# design.net
KiCad netlist of a schematic drawn in Altium Designer
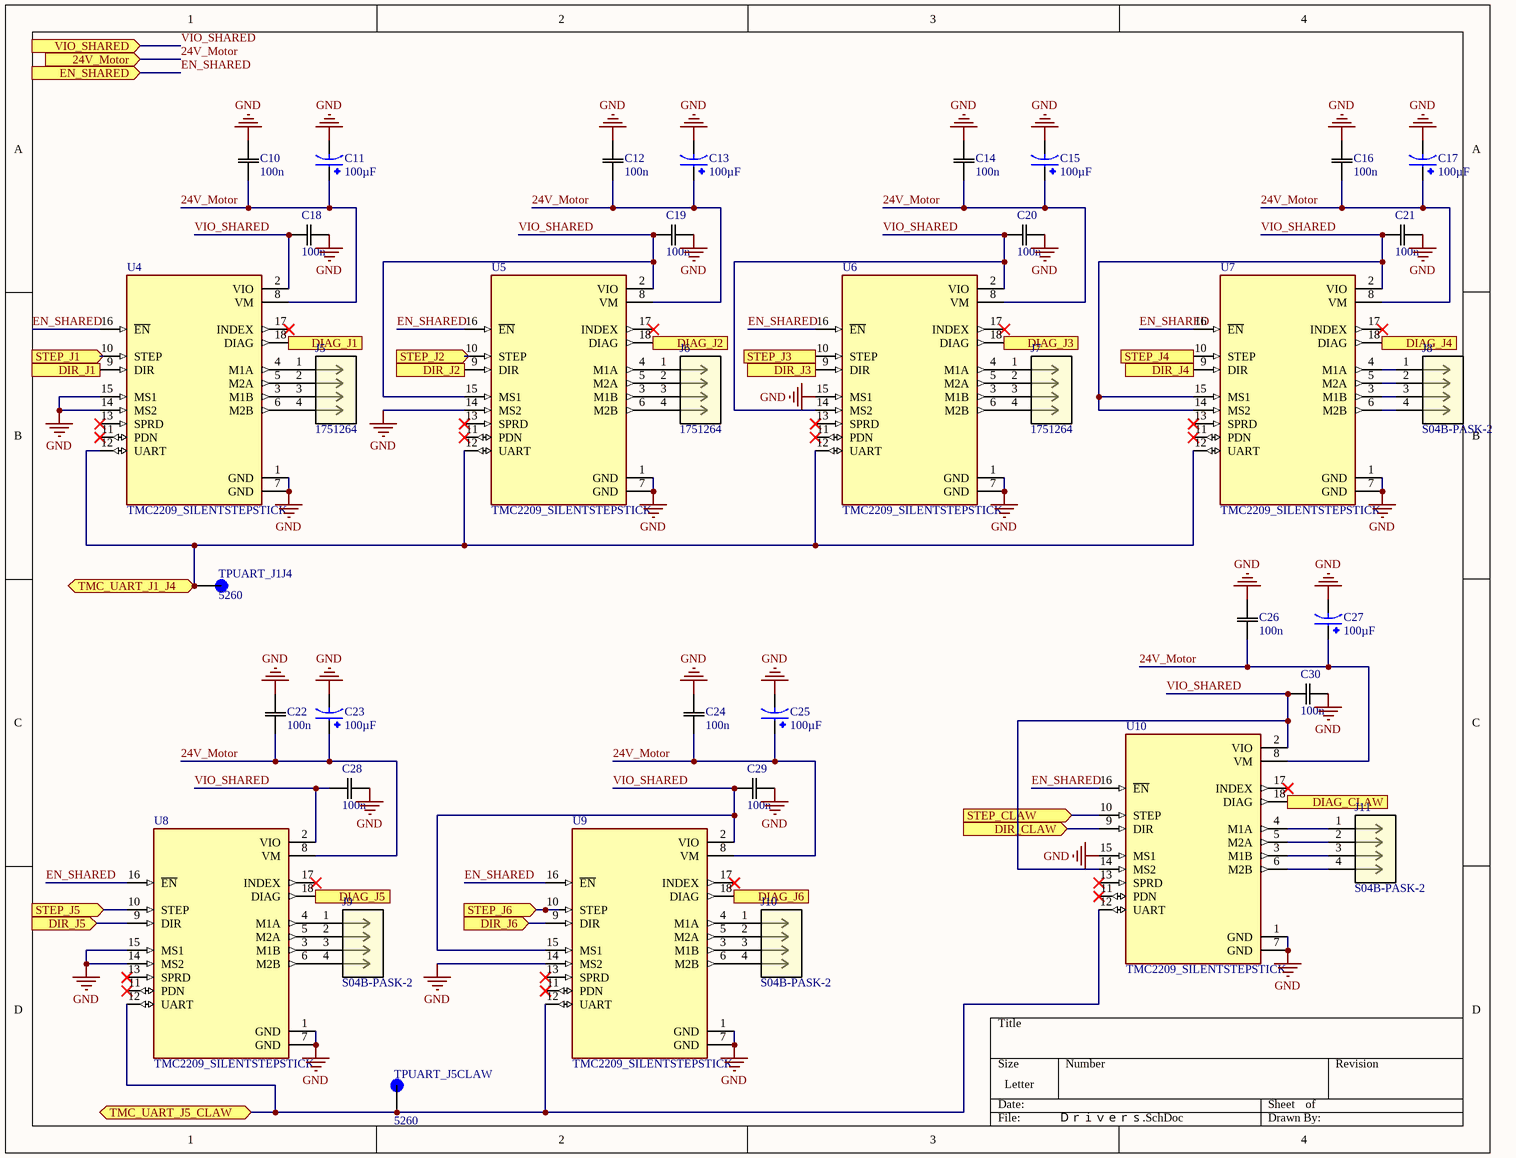
[diagram p0: Ｄｒｉｖｅｒｓ.SchDoc]

(export (version "E")
  (design (tool "Eeschema 10.0.6"))
  (components
    (comp (ref "C10")
      (value "CL21B104KCCWPNC")
      (footprint "CAP_CL_21_SAM")
      (description "No Description Available")
      (fields
        (field (name "CAPACITANCE") "100n")
        (field (name "COPYRIGHT") "Copyright (C) 2026 Ultra Librarian. All rights reserved.")
      )
      (libsource (lib "CL21B104KCCWPNC") (part "CL21B104KCCWPNC"))
    )
    (comp (ref "C11")
      (value "100µF")
      (footprint "CAPPRD500W60D800H1150")
      (description "Cap Aluminum 100uF 50V 20% (8 X 11.5mm) Radial 5mm 870mA 6000 hr 105C Ammo Pack")
      (fields (field (name "MP") "EEU-FR1H101B") (field (name "MF") "Panasonic Electronic"))
      (libsource (lib "Chen-Shi Liou") (part "EEUFR1H101B"))
    )
    (comp (ref "C12")
      (value "CL21B104KCCWPNC")
      (footprint "CAP_CL_21_SAM")
      (description "No Description Available")
      (fields
        (field (name "CAPACITANCE") "100n")
        (field (name "COPYRIGHT") "Copyright (C) 2026 Ultra Librarian. All rights reserved.")
      )
      (libsource (lib "CL21B104KCCWPNC") (part "CL21B104KCCWPNC"))
    )
    (comp (ref "C13")
      (value "100µF")
      (footprint "CAPPRD500W60D800H1150")
      (description "Cap Aluminum 100uF 50V 20% (8 X 11.5mm) Radial 5mm 870mA 6000 hr 105C Ammo Pack")
      (fields (field (name "MP") "EEU-FR1H101B") (field (name "MF") "Panasonic Electronic"))
      (libsource (lib "Chen-Shi Liou") (part "EEUFR1H101B"))
    )
    (comp (ref "C14")
      (value "CL21B104KCCWPNC")
      (footprint "CAP_CL_21_SAM")
      (description "No Description Available")
      (fields
        (field (name "CAPACITANCE") "100n")
        (field (name "COPYRIGHT") "Copyright (C) 2026 Ultra Librarian. All rights reserved.")
      )
      (libsource (lib "CL21B104KCCWPNC") (part "CL21B104KCCWPNC"))
    )
    (comp (ref "C15")
      (value "100µF")
      (footprint "CAPPRD500W60D800H1150")
      (description "Cap Aluminum 100uF 50V 20% (8 X 11.5mm) Radial 5mm 870mA 6000 hr 105C Ammo Pack")
      (fields (field (name "MP") "EEU-FR1H101B") (field (name "MF") "Panasonic Electronic"))
      (libsource (lib "Chen-Shi Liou") (part "EEUFR1H101B"))
    )
    (comp (ref "C16")
      (value "CL21B104KCCWPNC")
      (footprint "CAP_CL_21_SAM")
      (description "No Description Available")
      (fields
        (field (name "CAPACITANCE") "100n")
        (field (name "COPYRIGHT") "Copyright (C) 2026 Ultra Librarian. All rights reserved.")
      )
      (libsource (lib "CL21B104KCCWPNC") (part "CL21B104KCCWPNC"))
    )
    (comp (ref "C17")
      (value "100µF")
      (footprint "CAPPRD500W60D800H1150")
      (description "Cap Aluminum 100uF 50V 20% (8 X 11.5mm) Radial 5mm 870mA 6000 hr 105C Ammo Pack")
      (fields (field (name "MP") "EEU-FR1H101B") (field (name "MF") "Panasonic Electronic"))
      (libsource (lib "Chen-Shi Liou") (part "EEUFR1H101B"))
    )
    (comp (ref "C18")
      (value "CL21B104KCCWPNC")
      (footprint "CAP_CL_21_SAM")
      (description "No Description Available")
      (fields
        (field (name "CAPACITANCE") "100n")
        (field (name "COPYRIGHT") "Copyright (C) 2026 Ultra Librarian. All rights reserved.")
      )
      (libsource (lib "CL21B104KCCWPNC") (part "CL21B104KCCWPNC"))
    )
    (comp (ref "C19")
      (value "CL21B104KCCWPNC")
      (footprint "CAP_CL_21_SAM")
      (description "No Description Available")
      (fields
        (field (name "CAPACITANCE") "100n")
        (field (name "COPYRIGHT") "Copyright (C) 2026 Ultra Librarian. All rights reserved.")
      )
      (libsource (lib "CL21B104KCCWPNC") (part "CL21B104KCCWPNC"))
    )
    (comp (ref "C20")
      (value "CL21B104KCCWPNC")
      (footprint "CAP_CL_21_SAM")
      (description "No Description Available")
      (fields
        (field (name "CAPACITANCE") "100n")
        (field (name "COPYRIGHT") "Copyright (C) 2026 Ultra Librarian. All rights reserved.")
      )
      (libsource (lib "CL21B104KCCWPNC") (part "CL21B104KCCWPNC"))
    )
    (comp (ref "C21")
      (value "CL21B104KCCWPNC")
      (footprint "CAP_CL_21_SAM")
      (description "No Description Available")
      (fields
        (field (name "CAPACITANCE") "100n")
        (field (name "COPYRIGHT") "Copyright (C) 2026 Ultra Librarian. All rights reserved.")
      )
      (libsource (lib "CL21B104KCCWPNC") (part "CL21B104KCCWPNC"))
    )
    (comp (ref "C22")
      (value "CL21B104KCCWPNC")
      (footprint "CAP_CL_21_SAM")
      (description "No Description Available")
      (fields
        (field (name "CAPACITANCE") "100n")
        (field (name "COPYRIGHT") "Copyright (C) 2026 Ultra Librarian. All rights reserved.")
      )
      (libsource (lib "CL21B104KCCWPNC") (part "CL21B104KCCWPNC"))
    )
    (comp (ref "C23")
      (value "100µF")
      (footprint "CAPPRD500W60D800H1150")
      (description "Cap Aluminum 100uF 50V 20% (8 X 11.5mm) Radial 5mm 870mA 6000 hr 105C Ammo Pack")
      (fields (field (name "MP") "EEU-FR1H101B") (field (name "MF") "Panasonic Electronic"))
      (libsource (lib "Chen-Shi Liou") (part "EEUFR1H101B"))
    )
    (comp (ref "C24")
      (value "CL21B104KCCWPNC")
      (footprint "CAP_CL_21_SAM")
      (description "No Description Available")
      (fields
        (field (name "CAPACITANCE") "100n")
        (field (name "COPYRIGHT") "Copyright (C) 2026 Ultra Librarian. All rights reserved.")
      )
      (libsource (lib "CL21B104KCCWPNC") (part "CL21B104KCCWPNC"))
    )
    (comp (ref "C25")
      (value "100µF")
      (footprint "CAPPRD500W60D800H1150")
      (description "Cap Aluminum 100uF 50V 20% (8 X 11.5mm) Radial 5mm 870mA 6000 hr 105C Ammo Pack")
      (fields (field (name "MP") "EEU-FR1H101B") (field (name "MF") "Panasonic Electronic"))
      (libsource (lib "Chen-Shi Liou") (part "EEUFR1H101B"))
    )
    (comp (ref "C26")
      (value "CL21B104KCCWPNC")
      (footprint "CAP_CL_21_SAM")
      (description "No Description Available")
      (fields
        (field (name "CAPACITANCE") "100n")
        (field (name "COPYRIGHT") "Copyright (C) 2026 Ultra Librarian. All rights reserved.")
      )
      (libsource (lib "CL21B104KCCWPNC") (part "CL21B104KCCWPNC"))
    )
    (comp (ref "C27")
      (value "100µF")
      (footprint "CAPPRD500W60D800H1150")
      (description "Cap Aluminum 100uF 50V 20% (8 X 11.5mm) Radial 5mm 870mA 6000 hr 105C Ammo Pack")
      (fields (field (name "MP") "EEU-FR1H101B") (field (name "MF") "Panasonic Electronic"))
      (libsource (lib "Chen-Shi Liou") (part "EEUFR1H101B"))
    )
    (comp (ref "C28")
      (value "CL21B104KCCWPNC")
      (footprint "CAP_CL_21_SAM")
      (description "No Description Available")
      (fields
        (field (name "CAPACITANCE") "100n")
        (field (name "COPYRIGHT") "Copyright (C) 2026 Ultra Librarian. All rights reserved.")
      )
      (libsource (lib "CL21B104KCCWPNC") (part "CL21B104KCCWPNC"))
    )
    (comp (ref "C29")
      (value "CL21B104KCCWPNC")
      (footprint "CAP_CL_21_SAM")
      (description "No Description Available")
      (fields
        (field (name "CAPACITANCE") "100n")
        (field (name "COPYRIGHT") "Copyright (C) 2026 Ultra Librarian. All rights reserved.")
      )
      (libsource (lib "CL21B104KCCWPNC") (part "CL21B104KCCWPNC"))
    )
    (comp (ref "C30")
      (value "CL21B104KCCWPNC")
      (footprint "CAP_CL_21_SAM")
      (description "No Description Available")
      (fields
        (field (name "CAPACITANCE") "100n")
        (field (name "COPYRIGHT") "Copyright (C) 2026 Ultra Librarian. All rights reserved.")
      )
      (libsource (lib "CL21B104KCCWPNC") (part "CL21B104KCCWPNC"))
    )
    (comp (ref "J5")
      (value "1751264")
      (footprint "CONN_1751264_PXC")
      (fields (field (name "COPYRIGHT") "Copyright (C) 2025 Ultra Librarian. All rights reserved."))
      (libsource (lib "1751264") (part "1751264"))
    )
    (comp (ref "J6")
      (value "1751264")
      (footprint "CONN_1751264_PXC")
      (fields (field (name "COPYRIGHT") "Copyright (C) 2025 Ultra Librarian. All rights reserved."))
      (libsource (lib "1751264") (part "1751264"))
    )
    (comp (ref "J7")
      (value "1751264")
      (footprint "CONN_1751264_PXC")
      (fields (field (name "COPYRIGHT") "Copyright (C) 2025 Ultra Librarian. All rights reserved."))
      (libsource (lib "1751264") (part "1751264"))
    )
    (comp (ref "J8")
      (value "S04B-PASK-2")
      (footprint "CONN4_S04B-PASK_JST")
      (description "Description")
      (fields (field (name "COPYRIGHT") "Copyright (C) 2025 Ultra Librarian. All rights reserved."))
      (libsource (lib "S04B-PASK-2") (part "S04B-PASK-2"))
    )
    (comp (ref "J9")
      (value "S04B-PASK-2")
      (footprint "CONN4_S04B-PASK_JST")
      (description "Description")
      (fields (field (name "COPYRIGHT") "Copyright (C) 2025 Ultra Librarian. All rights reserved."))
      (libsource (lib "S04B-PASK-2") (part "S04B-PASK-2"))
    )
    (comp (ref "J10")
      (value "S04B-PASK-2")
      (footprint "CONN4_S04B-PASK_JST")
      (description "Description")
      (fields (field (name "COPYRIGHT") "Copyright (C) 2025 Ultra Librarian. All rights reserved."))
      (libsource (lib "S04B-PASK-2") (part "S04B-PASK-2"))
    )
    (comp (ref "J11")
      (value "S04B-PASK-2")
      (footprint "CONN4_S04B-PASK_JST")
      (description "Description")
      (fields (field (name "COPYRIGHT") "Copyright (C) 2025 Ultra Librarian. All rights reserved."))
      (libsource (lib "S04B-PASK-2") (part "S04B-PASK-2"))
    )
    (comp (ref "TPUART_J1J4")
      (value "5260")
      (footprint "KEYSTONE_5260")
      (description "TEST POINT (RED) - MINIATURE")
      (fields (field (name "MF") "Keystone Electronics"))
      (libsource (lib "Chen-Shi Liou") (part "5260"))
    )
    (comp (ref "TPUART_J5CLAW")
      (value "5260")
      (footprint "KEYSTONE_5260")
      (description "TEST POINT (RED) - MINIATURE")
      (fields (field (name "MF") "Keystone Electronics"))
      (libsource (lib "Chen-Shi Liou") (part "5260"))
    )
    (comp (ref "U4")
      (value "TMC2209_SILENTSTEPSTICK")
      (footprint "MODULE_TMC2209_SILENTSTEPSTICK")
      (description "TMC2209 Motor Controller/Driver Power Management Evaluation Board")
      (fields
        (field (name "MP") "TMC2209 SILENTSTEPSTICK")
        (field (name "MF") "Trinamic Motion Control GmbH")
      )
      (libsource (lib "Chen-Shi Liou") (part "TMC2209_SILENTSTEPSTICK"))
    )
    (comp (ref "U5")
      (value "TMC2209_SILENTSTEPSTICK")
      (footprint "MODULE_TMC2209_SILENTSTEPSTICK")
      (description "TMC2209 Motor Controller/Driver Power Management Evaluation Board")
      (fields
        (field (name "MP") "TMC2209 SILENTSTEPSTICK")
        (field (name "MF") "Trinamic Motion Control GmbH")
      )
      (libsource (lib "Chen-Shi Liou") (part "TMC2209_SILENTSTEPSTICK"))
    )
    (comp (ref "U6")
      (value "TMC2209_SILENTSTEPSTICK")
      (footprint "MODULE_TMC2209_SILENTSTEPSTICK")
      (description "TMC2209 Motor Controller/Driver Power Management Evaluation Board")
      (fields
        (field (name "MP") "TMC2209 SILENTSTEPSTICK")
        (field (name "MF") "Trinamic Motion Control GmbH")
      )
      (libsource (lib "Chen-Shi Liou") (part "TMC2209_SILENTSTEPSTICK"))
    )
    (comp (ref "U7")
      (value "TMC2209_SILENTSTEPSTICK")
      (footprint "MODULE_TMC2209_SILENTSTEPSTICK")
      (description "TMC2209 Motor Controller/Driver Power Management Evaluation Board")
      (fields
        (field (name "MP") "TMC2209 SILENTSTEPSTICK")
        (field (name "MF") "Trinamic Motion Control GmbH")
      )
      (libsource (lib "Chen-Shi Liou") (part "TMC2209_SILENTSTEPSTICK"))
    )
    (comp (ref "U8")
      (value "TMC2209_SILENTSTEPSTICK")
      (footprint "MODULE_TMC2209_SILENTSTEPSTICK")
      (description "TMC2209 Motor Controller/Driver Power Management Evaluation Board")
      (fields
        (field (name "MP") "TMC2209 SILENTSTEPSTICK")
        (field (name "MF") "Trinamic Motion Control GmbH")
      )
      (libsource (lib "Chen-Shi Liou") (part "TMC2209_SILENTSTEPSTICK"))
    )
    (comp (ref "U9")
      (value "TMC2209_SILENTSTEPSTICK")
      (footprint "MODULE_TMC2209_SILENTSTEPSTICK")
      (description "TMC2209 Motor Controller/Driver Power Management Evaluation Board")
      (fields
        (field (name "MP") "TMC2209 SILENTSTEPSTICK")
        (field (name "MF") "Trinamic Motion Control GmbH")
      )
      (libsource (lib "Chen-Shi Liou") (part "TMC2209_SILENTSTEPSTICK"))
    )
    (comp (ref "U10")
      (value "TMC2209_SILENTSTEPSTICK")
      (footprint "MODULE_TMC2209_SILENTSTEPSTICK")
      (description "TMC2209 Motor Controller/Driver Power Management Evaluation Board")
      (fields
        (field (name "MP") "TMC2209 SILENTSTEPSTICK")
        (field (name "MF") "Trinamic Motion Control GmbH")
      )
      (libsource (lib "Chen-Shi Liou") (part "TMC2209_SILENTSTEPSTICK"))
    )
  )
  (nets
    (net (code "1") (name "/24V_Motor") (class "Default")
      (node (ref "C10") (pin "1") (pinfunction "1_1") (pintype "passive"))
      (node (ref "C11") (pin "P") (pinfunction "P_P") (pintype "passive"))
      (node (ref "C12") (pin "1") (pinfunction "1_1") (pintype "passive"))
      (node (ref "C13") (pin "P") (pinfunction "P_P") (pintype "passive"))
      (node (ref "C14") (pin "1") (pinfunction "1_1") (pintype "passive"))
      (node (ref "C15") (pin "P") (pinfunction "P_P") (pintype "passive"))
      (node (ref "C16") (pin "1") (pinfunction "1_1") (pintype "passive"))
      (node (ref "C17") (pin "P") (pinfunction "P_P") (pintype "passive"))
      (node (ref "C22") (pin "1") (pinfunction "1_1") (pintype "passive"))
      (node (ref "C23") (pin "P") (pinfunction "P_P") (pintype "passive"))
      (node (ref "C24") (pin "1") (pinfunction "1_1") (pintype "passive"))
      (node (ref "C25") (pin "P") (pinfunction "P_P") (pintype "passive"))
      (node (ref "C26") (pin "1") (pinfunction "1_1") (pintype "passive"))
      (node (ref "C27") (pin "P") (pinfunction "P_P") (pintype "passive"))
      (node (ref "U10") (pin "8") (pinfunction "VM_8") (pintype "power_in"))
      (node (ref "U4") (pin "8") (pinfunction "VM_8") (pintype "power_in"))
      (node (ref "U5") (pin "8") (pinfunction "VM_8") (pintype "power_in"))
      (node (ref "U6") (pin "8") (pinfunction "VM_8") (pintype "power_in"))
      (node (ref "U7") (pin "8") (pinfunction "VM_8") (pintype "power_in"))
      (node (ref "U8") (pin "8") (pinfunction "VM_8") (pintype "power_in"))
      (node (ref "U9") (pin "8") (pinfunction "VM_8") (pintype "power_in"))
    )
    (net (code "2") (name "/DIAG_CLAW") (class "Default")
      (node (ref "U10") (pin "18") (pinfunction "DIAG_18") (pintype "output"))
    )
    (net (code "3") (name "/DIAG_J1") (class "Default")
      (node (ref "U4") (pin "18") (pinfunction "DIAG_18") (pintype "output"))
    )
    (net (code "4") (name "/DIAG_J2") (class "Default")
      (node (ref "U5") (pin "18") (pinfunction "DIAG_18") (pintype "output"))
    )
    (net (code "5") (name "/DIAG_J3") (class "Default")
      (node (ref "U6") (pin "18") (pinfunction "DIAG_18") (pintype "output"))
    )
    (net (code "6") (name "/DIAG_J4") (class "Default")
      (node (ref "U7") (pin "18") (pinfunction "DIAG_18") (pintype "output"))
    )
    (net (code "7") (name "/DIAG_J5") (class "Default")
      (node (ref "U8") (pin "18") (pinfunction "DIAG_18") (pintype "output"))
    )
    (net (code "8") (name "/DIAG_J6") (class "Default")
      (node (ref "U9") (pin "18") (pinfunction "DIAG_18") (pintype "output"))
    )
    (net (code "9") (name "/DIR_CLAW") (class "Default")
      (node (ref "U10") (pin "9") (pinfunction "DIR_9") (pintype "input"))
    )
    (net (code "10") (name "/DIR_J1") (class "Default")
      (node (ref "U4") (pin "9") (pinfunction "DIR_9") (pintype "input"))
    )
    (net (code "11") (name "/DIR_J2") (class "Default")
      (node (ref "U5") (pin "9") (pinfunction "DIR_9") (pintype "input"))
    )
    (net (code "12") (name "/DIR_J3") (class "Default")
      (node (ref "U6") (pin "9") (pinfunction "DIR_9") (pintype "input"))
    )
    (net (code "13") (name "/DIR_J4") (class "Default")
      (node (ref "U7") (pin "9") (pinfunction "DIR_9") (pintype "input"))
    )
    (net (code "14") (name "/DIR_J5") (class "Default")
      (node (ref "U8") (pin "9") (pinfunction "DIR_9") (pintype "input"))
    )
    (net (code "15") (name "/DIR_J6") (class "Default")
      (node (ref "U9") (pin "9") (pinfunction "DIR_9") (pintype "input"))
    )
    (net (code "16") (name "/EN_SHARED") (class "Default")
      (node (ref "U10") (pin "16") (pinfunction "~{EN}_16") (pintype "input"))
      (node (ref "U4") (pin "16") (pinfunction "~{EN}_16") (pintype "input"))
      (node (ref "U5") (pin "16") (pinfunction "~{EN}_16") (pintype "input"))
      (node (ref "U6") (pin "16") (pinfunction "~{EN}_16") (pintype "input"))
      (node (ref "U7") (pin "16") (pinfunction "~{EN}_16") (pintype "input"))
      (node (ref "U8") (pin "16") (pinfunction "~{EN}_16") (pintype "input"))
      (node (ref "U9") (pin "16") (pinfunction "~{EN}_16") (pintype "input"))
    )
    (net (code "17") (name "/STEP_CLAW") (class "Default")
      (node (ref "U10") (pin "10") (pinfunction "STEP_10") (pintype "input"))
    )
    (net (code "18") (name "/STEP_J1") (class "Default")
      (node (ref "U4") (pin "10") (pinfunction "STEP_10") (pintype "input"))
    )
    (net (code "19") (name "/STEP_J2") (class "Default")
      (node (ref "U5") (pin "10") (pinfunction "STEP_10") (pintype "input"))
    )
    (net (code "20") (name "/STEP_J3") (class "Default")
      (node (ref "U6") (pin "10") (pinfunction "STEP_10") (pintype "input"))
    )
    (net (code "21") (name "/STEP_J4") (class "Default")
      (node (ref "U7") (pin "10") (pinfunction "STEP_10") (pintype "input"))
    )
    (net (code "22") (name "/STEP_J5") (class "Default")
      (node (ref "U8") (pin "10") (pinfunction "STEP_10") (pintype "input"))
    )
    (net (code "23") (name "/STEP_J6") (class "Default")
      (node (ref "U9") (pin "10") (pinfunction "STEP_10") (pintype "input"))
    )
    (net (code "24") (name "/TMC_UART_J1_J4") (class "Default")
      (node (ref "TPUART_J1J4") (pin "1") (pinfunction "TP_1") (pintype "passive"))
      (node (ref "U4") (pin "12") (pinfunction "UART_12") (pintype "bidirectional"))
      (node (ref "U5") (pin "12") (pinfunction "UART_12") (pintype "bidirectional"))
      (node (ref "U6") (pin "12") (pinfunction "UART_12") (pintype "bidirectional"))
      (node (ref "U7") (pin "12") (pinfunction "UART_12") (pintype "bidirectional"))
    )
    (net (code "25") (name "/TMC_UART_J5_CLAW") (class "Default")
      (node (ref "TPUART_J5CLAW") (pin "1") (pinfunction "TP_1") (pintype "passive"))
      (node (ref "U10") (pin "12") (pinfunction "UART_12") (pintype "bidirectional"))
      (node (ref "U8") (pin "12") (pinfunction "UART_12") (pintype "bidirectional"))
      (node (ref "U9") (pin "12") (pinfunction "UART_12") (pintype "bidirectional"))
    )
    (net (code "26") (name "/VIO_SHARED") (class "Default")
      (node (ref "C18") (pin "1") (pinfunction "1_1") (pintype "passive"))
      (node (ref "C19") (pin "1") (pinfunction "1_1") (pintype "passive"))
      (node (ref "C20") (pin "1") (pinfunction "1_1") (pintype "passive"))
      (node (ref "C21") (pin "1") (pinfunction "1_1") (pintype "passive"))
      (node (ref "C28") (pin "1") (pinfunction "1_1") (pintype "passive"))
      (node (ref "C29") (pin "1") (pinfunction "1_1") (pintype "passive"))
      (node (ref "C30") (pin "1") (pinfunction "1_1") (pintype "passive"))
      (node (ref "U10") (pin "14") (pinfunction "MS2_14") (pintype "input"))
      (node (ref "U10") (pin "2") (pinfunction "VIO_2") (pintype "power_in"))
      (node (ref "U4") (pin "2") (pinfunction "VIO_2") (pintype "power_in"))
      (node (ref "U5") (pin "15") (pinfunction "MS1_15") (pintype "input"))
      (node (ref "U5") (pin "2") (pinfunction "VIO_2") (pintype "power_in"))
      (node (ref "U6") (pin "14") (pinfunction "MS2_14") (pintype "input"))
      (node (ref "U6") (pin "2") (pinfunction "VIO_2") (pintype "power_in"))
      (node (ref "U7") (pin "14") (pinfunction "MS2_14") (pintype "input"))
      (node (ref "U7") (pin "15") (pinfunction "MS1_15") (pintype "input"))
      (node (ref "U7") (pin "2") (pinfunction "VIO_2") (pintype "power_in"))
      (node (ref "U8") (pin "2") (pinfunction "VIO_2") (pintype "power_in"))
      (node (ref "U9") (pin "15") (pinfunction "MS1_15") (pintype "input"))
      (node (ref "U9") (pin "2") (pinfunction "VIO_2") (pintype "power_in"))
    )
    (net (code "27") (name "GND") (class "Default")
      (node (ref "C10") (pin "2") (pinfunction "2_2") (pintype "passive"))
      (node (ref "C11") (pin "N") (pinfunction "N_N") (pintype "passive"))
      (node (ref "C12") (pin "2") (pinfunction "2_2") (pintype "passive"))
      (node (ref "C13") (pin "N") (pinfunction "N_N") (pintype "passive"))
      (node (ref "C14") (pin "2") (pinfunction "2_2") (pintype "passive"))
      (node (ref "C15") (pin "N") (pinfunction "N_N") (pintype "passive"))
      (node (ref "C16") (pin "2") (pinfunction "2_2") (pintype "passive"))
      (node (ref "C17") (pin "N") (pinfunction "N_N") (pintype "passive"))
      (node (ref "C18") (pin "2") (pinfunction "2_2") (pintype "passive"))
      (node (ref "C19") (pin "2") (pinfunction "2_2") (pintype "passive"))
      (node (ref "C20") (pin "2") (pinfunction "2_2") (pintype "passive"))
      (node (ref "C21") (pin "2") (pinfunction "2_2") (pintype "passive"))
      (node (ref "C22") (pin "2") (pinfunction "2_2") (pintype "passive"))
      (node (ref "C23") (pin "N") (pinfunction "N_N") (pintype "passive"))
      (node (ref "C24") (pin "2") (pinfunction "2_2") (pintype "passive"))
      (node (ref "C25") (pin "N") (pinfunction "N_N") (pintype "passive"))
      (node (ref "C26") (pin "2") (pinfunction "2_2") (pintype "passive"))
      (node (ref "C27") (pin "N") (pinfunction "N_N") (pintype "passive"))
      (node (ref "C28") (pin "2") (pinfunction "2_2") (pintype "passive"))
      (node (ref "C29") (pin "2") (pinfunction "2_2") (pintype "passive"))
      (node (ref "C30") (pin "2") (pinfunction "2_2") (pintype "passive"))
      (node (ref "U10") (pin "1") (pinfunction "GND_1") (pintype "power_in"))
      (node (ref "U10") (pin "15") (pinfunction "MS1_15") (pintype "input"))
      (node (ref "U10") (pin "7") (pinfunction "GND_7") (pintype "power_in"))
      (node (ref "U4") (pin "1") (pinfunction "GND_1") (pintype "power_in"))
      (node (ref "U4") (pin "14") (pinfunction "MS2_14") (pintype "input"))
      (node (ref "U4") (pin "15") (pinfunction "MS1_15") (pintype "input"))
      (node (ref "U4") (pin "7") (pinfunction "GND_7") (pintype "power_in"))
      (node (ref "U5") (pin "1") (pinfunction "GND_1") (pintype "power_in"))
      (node (ref "U5") (pin "14") (pinfunction "MS2_14") (pintype "input"))
      (node (ref "U5") (pin "7") (pinfunction "GND_7") (pintype "power_in"))
      (node (ref "U6") (pin "1") (pinfunction "GND_1") (pintype "power_in"))
      (node (ref "U6") (pin "15") (pinfunction "MS1_15") (pintype "input"))
      (node (ref "U6") (pin "7") (pinfunction "GND_7") (pintype "power_in"))
      (node (ref "U7") (pin "1") (pinfunction "GND_1") (pintype "power_in"))
      (node (ref "U7") (pin "7") (pinfunction "GND_7") (pintype "power_in"))
      (node (ref "U8") (pin "1") (pinfunction "GND_1") (pintype "power_in"))
      (node (ref "U8") (pin "14") (pinfunction "MS2_14") (pintype "input"))
      (node (ref "U8") (pin "15") (pinfunction "MS1_15") (pintype "input"))
      (node (ref "U8") (pin "7") (pinfunction "GND_7") (pintype "power_in"))
      (node (ref "U9") (pin "1") (pinfunction "GND_1") (pintype "power_in"))
      (node (ref "U9") (pin "14") (pinfunction "MS2_14") (pintype "input"))
      (node (ref "U9") (pin "7") (pinfunction "GND_7") (pintype "power_in"))
    )
    (net (code "28") (name "Net-(U4-M1A)") (class "Default")
      (node (ref "J5") (pin "1") (pinfunction "1_1") (pintype "passive"))
      (node (ref "U4") (pin "4") (pinfunction "M1A_4") (pintype "output"))
    )
    (net (code "29") (name "Net-(U4-M1B)") (class "Default")
      (node (ref "J5") (pin "3") (pinfunction "3_3") (pintype "passive"))
      (node (ref "U4") (pin "3") (pinfunction "M1B_3") (pintype "output"))
    )
    (net (code "30") (name "Net-(U4-M2A)") (class "Default")
      (node (ref "J5") (pin "2") (pinfunction "2_2") (pintype "passive"))
      (node (ref "U4") (pin "5") (pinfunction "M2A_5") (pintype "output"))
    )
    (net (code "31") (name "Net-(U4-M2B)") (class "Default")
      (node (ref "J5") (pin "4") (pinfunction "4_4") (pintype "passive"))
      (node (ref "U4") (pin "6") (pinfunction "M2B_6") (pintype "output"))
    )
    (net (code "32") (name "Net-(U5-M1A)") (class "Default")
      (node (ref "J6") (pin "1") (pinfunction "1_1") (pintype "passive"))
      (node (ref "U5") (pin "4") (pinfunction "M1A_4") (pintype "output"))
    )
    (net (code "33") (name "Net-(U5-M1B)") (class "Default")
      (node (ref "J6") (pin "3") (pinfunction "3_3") (pintype "passive"))
      (node (ref "U5") (pin "3") (pinfunction "M1B_3") (pintype "output"))
    )
    (net (code "34") (name "Net-(U5-M2A)") (class "Default")
      (node (ref "J6") (pin "2") (pinfunction "2_2") (pintype "passive"))
      (node (ref "U5") (pin "5") (pinfunction "M2A_5") (pintype "output"))
    )
    (net (code "35") (name "Net-(U5-M2B)") (class "Default")
      (node (ref "J6") (pin "4") (pinfunction "4_4") (pintype "passive"))
      (node (ref "U5") (pin "6") (pinfunction "M2B_6") (pintype "output"))
    )
    (net (code "36") (name "Net-(U6-M1A)") (class "Default")
      (node (ref "J7") (pin "1") (pinfunction "1_1") (pintype "passive"))
      (node (ref "U6") (pin "4") (pinfunction "M1A_4") (pintype "output"))
    )
    (net (code "37") (name "Net-(U6-M1B)") (class "Default")
      (node (ref "J7") (pin "3") (pinfunction "3_3") (pintype "passive"))
      (node (ref "U6") (pin "3") (pinfunction "M1B_3") (pintype "output"))
    )
    (net (code "38") (name "Net-(U6-M2A)") (class "Default")
      (node (ref "J7") (pin "2") (pinfunction "2_2") (pintype "passive"))
      (node (ref "U6") (pin "5") (pinfunction "M2A_5") (pintype "output"))
    )
    (net (code "39") (name "Net-(U6-M2B)") (class "Default")
      (node (ref "J7") (pin "4") (pinfunction "4_4") (pintype "passive"))
      (node (ref "U6") (pin "6") (pinfunction "M2B_6") (pintype "output"))
    )
    (net (code "40") (name "Net-(U7-M1A)") (class "Default")
      (node (ref "J8") (pin "1") (pinfunction "1_1") (pintype "passive"))
      (node (ref "U7") (pin "4") (pinfunction "M1A_4") (pintype "output"))
    )
    (net (code "41") (name "Net-(U7-M1B)") (class "Default")
      (node (ref "J8") (pin "3") (pinfunction "3_3") (pintype "passive"))
      (node (ref "U7") (pin "3") (pinfunction "M1B_3") (pintype "output"))
    )
    (net (code "42") (name "Net-(U7-M2A)") (class "Default")
      (node (ref "J8") (pin "2") (pinfunction "2_2") (pintype "passive"))
      (node (ref "U7") (pin "5") (pinfunction "M2A_5") (pintype "output"))
    )
    (net (code "43") (name "Net-(U7-M2B)") (class "Default")
      (node (ref "J8") (pin "4") (pinfunction "4_4") (pintype "passive"))
      (node (ref "U7") (pin "6") (pinfunction "M2B_6") (pintype "output"))
    )
    (net (code "44") (name "Net-(U8-M1A)") (class "Default")
      (node (ref "J9") (pin "1") (pinfunction "1_1") (pintype "passive"))
      (node (ref "U8") (pin "4") (pinfunction "M1A_4") (pintype "output"))
    )
    (net (code "45") (name "Net-(U8-M1B)") (class "Default")
      (node (ref "J9") (pin "3") (pinfunction "3_3") (pintype "passive"))
      (node (ref "U8") (pin "3") (pinfunction "M1B_3") (pintype "output"))
    )
    (net (code "46") (name "Net-(U8-M2A)") (class "Default")
      (node (ref "J9") (pin "2") (pinfunction "2_2") (pintype "passive"))
      (node (ref "U8") (pin "5") (pinfunction "M2A_5") (pintype "output"))
    )
    (net (code "47") (name "Net-(U8-M2B)") (class "Default")
      (node (ref "J9") (pin "4") (pinfunction "4_4") (pintype "passive"))
      (node (ref "U8") (pin "6") (pinfunction "M2B_6") (pintype "output"))
    )
    (net (code "48") (name "Net-(U9-M1A)") (class "Default")
      (node (ref "J10") (pin "1") (pinfunction "1_1") (pintype "passive"))
      (node (ref "U9") (pin "4") (pinfunction "M1A_4") (pintype "output"))
    )
    (net (code "49") (name "Net-(U9-M1B)") (class "Default")
      (node (ref "J10") (pin "3") (pinfunction "3_3") (pintype "passive"))
      (node (ref "U9") (pin "3") (pinfunction "M1B_3") (pintype "output"))
    )
    (net (code "50") (name "Net-(U9-M2A)") (class "Default")
      (node (ref "J10") (pin "2") (pinfunction "2_2") (pintype "passive"))
      (node (ref "U9") (pin "5") (pinfunction "M2A_5") (pintype "output"))
    )
    (net (code "51") (name "Net-(U9-M2B)") (class "Default")
      (node (ref "J10") (pin "4") (pinfunction "4_4") (pintype "passive"))
      (node (ref "U9") (pin "6") (pinfunction "M2B_6") (pintype "output"))
    )
    (net (code "52") (name "Net-(U10-M1A)") (class "Default")
      (node (ref "J11") (pin "1") (pinfunction "1_1") (pintype "passive"))
      (node (ref "U10") (pin "4") (pinfunction "M1A_4") (pintype "output"))
    )
    (net (code "53") (name "Net-(U10-M1B)") (class "Default")
      (node (ref "J11") (pin "3") (pinfunction "3_3") (pintype "passive"))
      (node (ref "U10") (pin "3") (pinfunction "M1B_3") (pintype "output"))
    )
    (net (code "54") (name "Net-(U10-M2A)") (class "Default")
      (node (ref "J11") (pin "2") (pinfunction "2_2") (pintype "passive"))
      (node (ref "U10") (pin "5") (pinfunction "M2A_5") (pintype "output"))
    )
    (net (code "55") (name "Net-(U10-M2B)") (class "Default")
      (node (ref "J11") (pin "4") (pinfunction "4_4") (pintype "passive"))
      (node (ref "U10") (pin "6") (pinfunction "M2B_6") (pintype "output"))
    )
    (net (code "56") (name "unconnected-(U4-INDEX-Pad17)") (class "Default")
      (node (ref "U4") (pin "17") (pinfunction "INDEX_17") (pintype "output+no_connect"))
    )
    (net (code "57") (name "unconnected-(U4-PDN-Pad11)") (class "Default")
      (node (ref "U4") (pin "11") (pinfunction "PDN_11") (pintype "bidirectional+no_connect"))
    )
    (net (code "58") (name "unconnected-(U4-SPRD-Pad13)") (class "Default")
      (node (ref "U4") (pin "13") (pinfunction "SPRD_13") (pintype "input+no_connect"))
    )
    (net (code "59") (name "unconnected-(U5-INDEX-Pad17)") (class "Default")
      (node (ref "U5") (pin "17") (pinfunction "INDEX_17") (pintype "output+no_connect"))
    )
    (net (code "60") (name "unconnected-(U5-PDN-Pad11)") (class "Default")
      (node (ref "U5") (pin "11") (pinfunction "PDN_11") (pintype "bidirectional+no_connect"))
    )
    (net (code "61") (name "unconnected-(U5-SPRD-Pad13)") (class "Default")
      (node (ref "U5") (pin "13") (pinfunction "SPRD_13") (pintype "input+no_connect"))
    )
    (net (code "62") (name "unconnected-(U6-INDEX-Pad17)") (class "Default")
      (node (ref "U6") (pin "17") (pinfunction "INDEX_17") (pintype "output+no_connect"))
    )
    (net (code "63") (name "unconnected-(U6-PDN-Pad11)") (class "Default")
      (node (ref "U6") (pin "11") (pinfunction "PDN_11") (pintype "bidirectional+no_connect"))
    )
    (net (code "64") (name "unconnected-(U6-SPRD-Pad13)") (class "Default")
      (node (ref "U6") (pin "13") (pinfunction "SPRD_13") (pintype "input+no_connect"))
    )
    (net (code "65") (name "unconnected-(U7-INDEX-Pad17)") (class "Default")
      (node (ref "U7") (pin "17") (pinfunction "INDEX_17") (pintype "output+no_connect"))
    )
    (net (code "66") (name "unconnected-(U7-PDN-Pad11)") (class "Default")
      (node (ref "U7") (pin "11") (pinfunction "PDN_11") (pintype "bidirectional+no_connect"))
    )
    (net (code "67") (name "unconnected-(U7-SPRD-Pad13)") (class "Default")
      (node (ref "U7") (pin "13") (pinfunction "SPRD_13") (pintype "input+no_connect"))
    )
    (net (code "68") (name "unconnected-(U8-INDEX-Pad17)") (class "Default")
      (node (ref "U8") (pin "17") (pinfunction "INDEX_17") (pintype "output+no_connect"))
    )
    (net (code "69") (name "unconnected-(U8-PDN-Pad11)") (class "Default")
      (node (ref "U8") (pin "11") (pinfunction "PDN_11") (pintype "bidirectional+no_connect"))
    )
    (net (code "70") (name "unconnected-(U8-SPRD-Pad13)") (class "Default")
      (node (ref "U8") (pin "13") (pinfunction "SPRD_13") (pintype "input+no_connect"))
    )
    (net (code "71") (name "unconnected-(U9-INDEX-Pad17)") (class "Default")
      (node (ref "U9") (pin "17") (pinfunction "INDEX_17") (pintype "output+no_connect"))
    )
    (net (code "72") (name "unconnected-(U9-PDN-Pad11)") (class "Default")
      (node (ref "U9") (pin "11") (pinfunction "PDN_11") (pintype "bidirectional+no_connect"))
    )
    (net (code "73") (name "unconnected-(U9-SPRD-Pad13)") (class "Default")
      (node (ref "U9") (pin "13") (pinfunction "SPRD_13") (pintype "input+no_connect"))
    )
    (net (code "74") (name "unconnected-(U10-INDEX-Pad17)") (class "Default")
      (node (ref "U10") (pin "17") (pinfunction "INDEX_17") (pintype "output+no_connect"))
    )
    (net (code "75") (name "unconnected-(U10-PDN-Pad11)") (class "Default")
      (node (ref "U10") (pin "11") (pinfunction "PDN_11") (pintype "bidirectional+no_connect"))
    )
    (net (code "76") (name "unconnected-(U10-SPRD-Pad13)") (class "Default")
      (node (ref "U10") (pin "13") (pinfunction "SPRD_13") (pintype "input+no_connect"))
    )
  )
)
